# fan-host-board-v1_1-_WIP.net
KiCad netlist of a schematic drawn in EAGLE
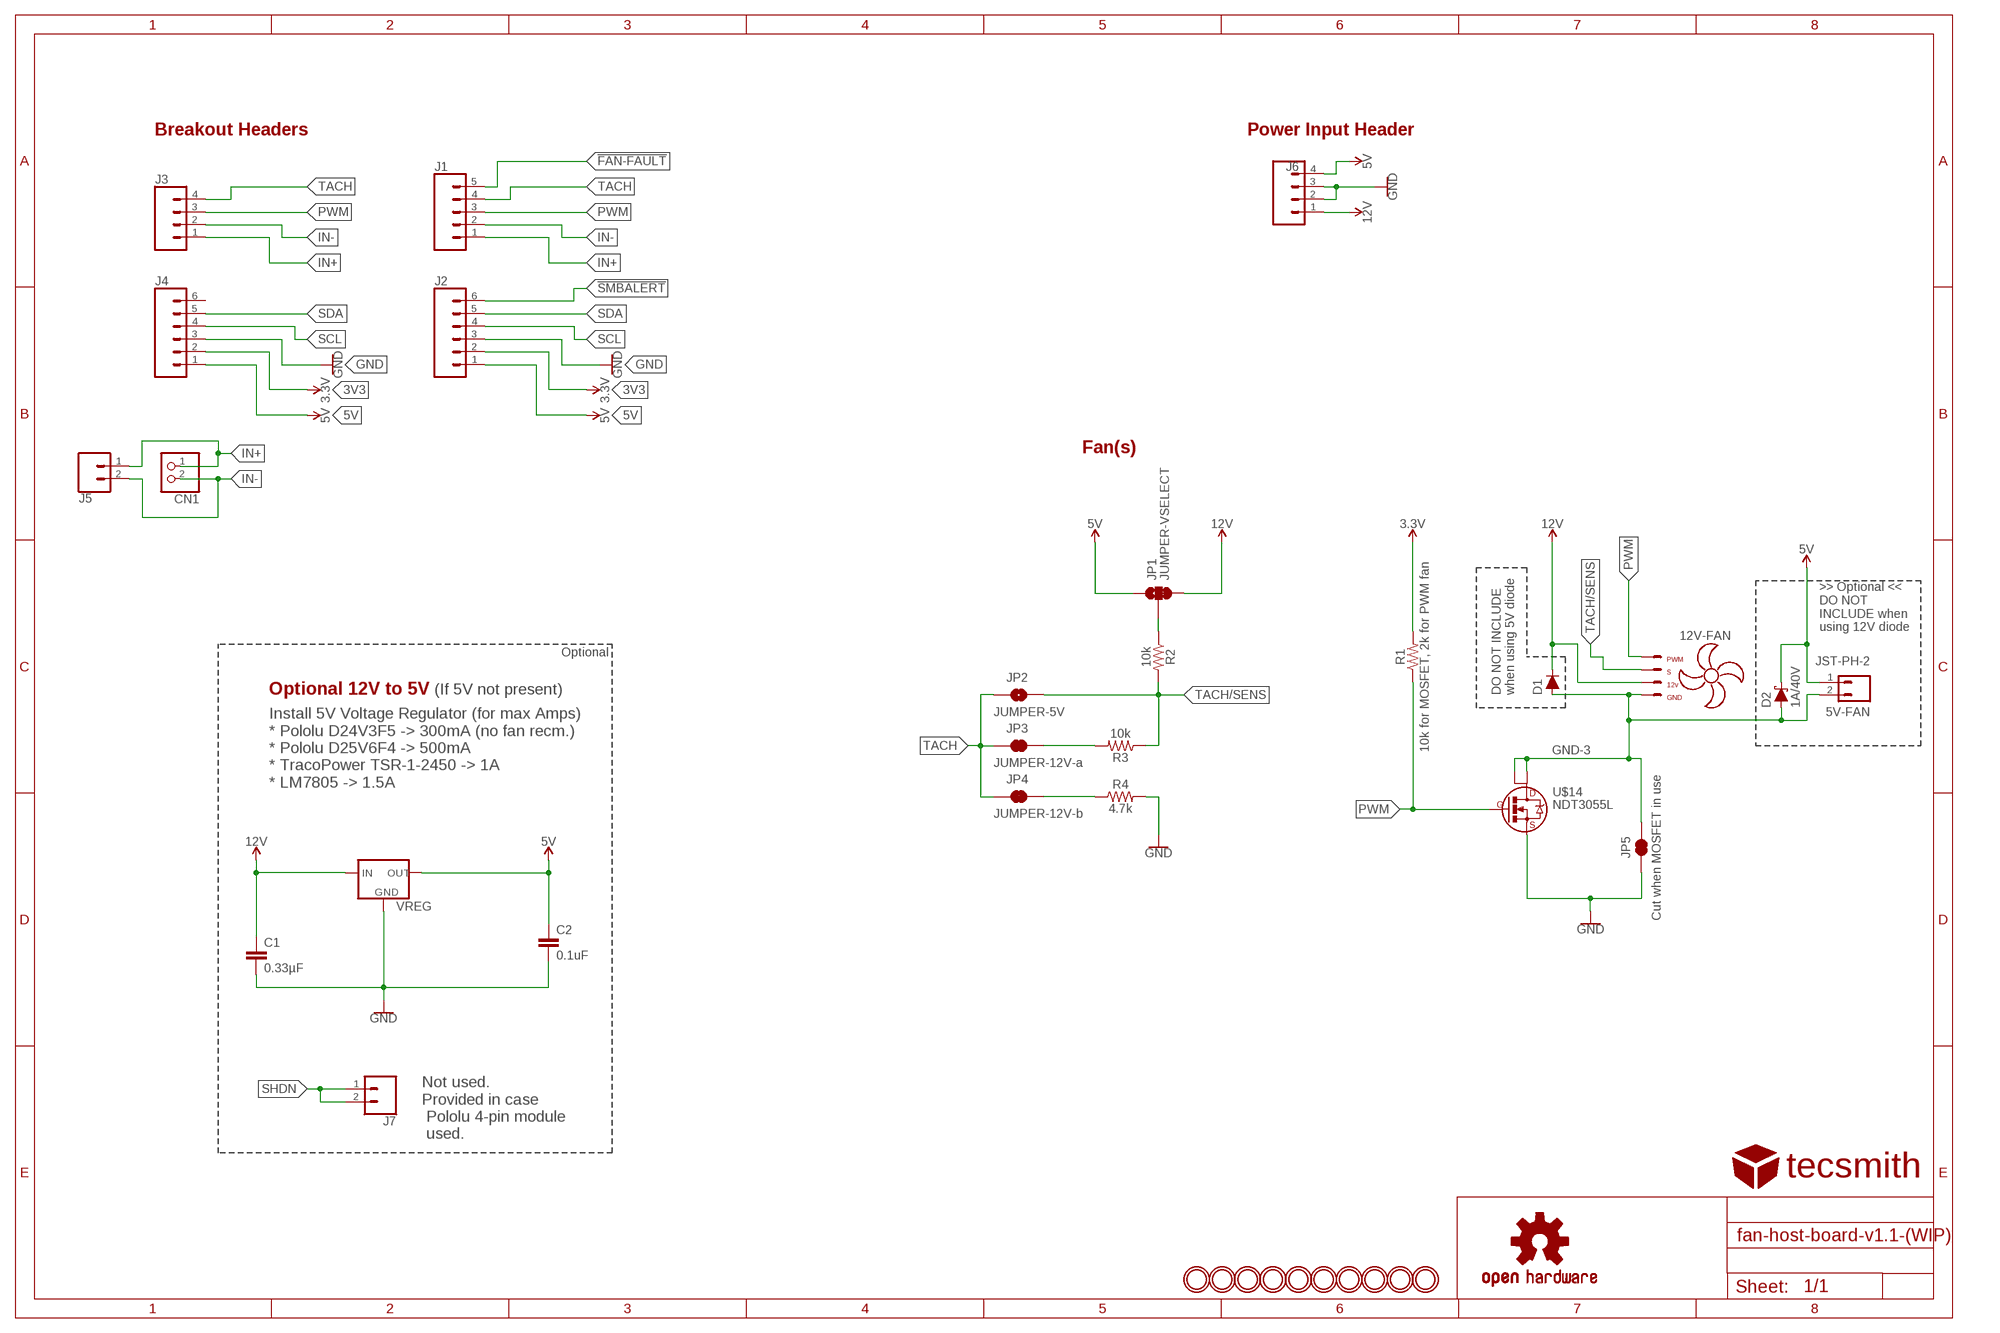
[diagram p0: schematic, sheet 1]

(export (version "E")
  (design (tool "Eeschema 10.0.6"))
  (components
    (comp (ref "5V-FAN")
      (value "JST-PH-2")
      (footprint "eagle-import:JST-PH2")
      (libsource (lib "eagle-import") (part "JST-PH-2"))
    )
    (comp (ref "12V-FAN")
      (value "KK-254-4KK-254")
      (footprint "eagle-import:MOLEX_47053-1000")
      (libsource (lib "eagle-import") (part "KK-254-4KK-254"))
    )
    (comp (ref "C1")
      (value "0.33µF")
      (footprint "eagle-import:0805")
      (libsource (lib "eagle-import") (part "0.33UF/330NF-0805-50V-10%"))
    )
    (comp (ref "C2")
      (value "0.1uF")
      (footprint "eagle-import:0603")
      (libsource (lib "eagle-import") (part "0.1UF-0603-25V-5%"))
    )
    (comp (ref "CN1")
      (value "JST_2PIN-THM")
      (footprint "eagle-import:JST-PH-2-THM")
      (libsource (lib "eagle-import") (part "JST_2PIN-THM"))
    )
    (comp (ref "D1")
      (value "200mA/100V")
      (footprint "eagle-import:DIODE-1N4148")
      (libsource (lib "eagle-import") (part "DIODE-1N4148"))
    )
    (comp (ref "D2")
      (value "1A/40V")
      (footprint "eagle-import:SMA-DIODE")
      (libsource (lib "eagle-import") (part "DIODE-SCHOTTKY-SS14"))
    )
    (comp (ref "J1")
      (value "CONN_05")
      (footprint "eagle-import:1X05")
      (libsource (lib "eagle-import") (part "CONN_05"))
    )
    (comp (ref "J2")
      (value "CONN_06SILK_FEMALE_PTH")
      (footprint "eagle-import:1X06")
      (libsource (lib "eagle-import") (part "CONN_06SILK_FEMALE_PTH"))
    )
    (comp (ref "J3")
      (value "CONN_04PTH")
      (footprint "eagle-import:1X04")
      (libsource (lib "eagle-import") (part "CONN_04PTH"))
    )
    (comp (ref "J4")
      (value "CONN_06SILK_FEMALE_PTH")
      (footprint "eagle-import:1X06")
      (libsource (lib "eagle-import") (part "CONN_06SILK_FEMALE_PTH"))
    )
    (comp (ref "J5")
      (value "CONN_02PTH3")
      (footprint "eagle-import:1X02_LONGPADS")
      (libsource (lib "eagle-import") (part "CONN_02PTH3"))
    )
    (comp (ref "J6")
      (value "CONN_04SCREW")
      (footprint "eagle-import:SCREWTERMINAL-3.5MM-4")
      (libsource (lib "eagle-import") (part "CONN_04SCREW"))
    )
    (comp (ref "J7")
      (value "CONN_021X02_NO_SILK")
      (footprint "eagle-import:1X02_NO_SILK")
      (libsource (lib "eagle-import") (part "CONN_021X02_NO_SILK"))
    )
    (comp (ref "JP1")
      (value "JUMPER-VSELECT")
      (footprint "eagle-import:SMT-JUMPER_3_1-NC_TRACE_SILK")
      (libsource (lib "eagle-import") (part "JUMPER-SMT_3_1-NC_TRACE_SILK"))
    )
    (comp (ref "JP2")
      (value "JUMPER-5V")
      (footprint "eagle-import:SMT-JUMPER_2_NO_SILK")
      (libsource (lib "eagle-import") (part "JUMPER-SMT_2_NO_NO_SILK"))
    )
    (comp (ref "JP3")
      (value "JUMPER-12V-a")
      (footprint "eagle-import:SMT-JUMPER_2_NC_TRACE_SILK")
      (libsource (lib "eagle-import") (part "JUMPER-SMT_2_NC_TRACE_SILK"))
    )
    (comp (ref "JP4")
      (value "JUMPER-12V-b")
      (footprint "eagle-import:SMT-JUMPER_2_NC_TRACE_SILK")
      (libsource (lib "eagle-import") (part "JUMPER-SMT_2_NC_TRACE_SILK"))
    )
    (comp (ref "JP5")
      (value "Cut when MOSFET in use")
      (footprint "eagle-import:SMT-JUMPER_2_NC_TRACE_NO-SILK")
      (libsource (lib "eagle-import") (part "JUMPER-SMT_2_NC_TRACE_NO-SILK"))
    )
    (comp (ref "LOGO1")
      (value "OSHW-LOGOS")
      (footprint "eagle-import:OSHW-LOGO-S")
      (libsource (lib "eagle-import") (part "OSHW-LOGOS"))
    )
    (comp (ref "R1")
      (value "10k for MOSFET, 2k for PWM fan")
      (footprint "eagle-import:0603")
      (libsource (lib "eagle-import") (part "2.2KOHM-0603-1/10W-1%"))
    )
    (comp (ref "R2")
      (value "10k")
      (footprint "eagle-import:0603")
      (libsource (lib "eagle-import") (part "10KOHM-0603-1/10W-1%"))
    )
    (comp (ref "R3")
      (value "10k")
      (footprint "eagle-import:0603")
      (libsource (lib "eagle-import") (part "10KOHM-0603-1/10W-1%"))
    )
    (comp (ref "R4")
      (value "4.7k")
      (footprint "eagle-import:0603")
      (libsource (lib "eagle-import") (part "4.7KOHM-0603-1/10W-1%"))
    )
    (comp (ref "U$1")
      (value "TECSMITH-LOGO")
      (footprint "eagle-import:TECSMITH-LOGO")
      (libsource (lib "eagle-import") (part "TECSMITH-LOGO"))
    )
    (comp (ref "U$2")
      (value "MOUNTINGHOLE2.5")
      (footprint "eagle-import:MOUNTINGHOLE_2.5_PLATED")
      (libsource (lib "eagle-import") (part "MOUNTINGHOLE2.5"))
    )
    (comp (ref "U$3")
      (value "MOUNTINGHOLE2.5")
      (footprint "eagle-import:MOUNTINGHOLE_2.5_PLATED")
      (libsource (lib "eagle-import") (part "MOUNTINGHOLE2.5"))
    )
    (comp (ref "U$4")
      (value "MOUNTINGHOLE2.5")
      (footprint "eagle-import:MOUNTINGHOLE_2.5_PLATED")
      (libsource (lib "eagle-import") (part "MOUNTINGHOLE2.5"))
    )
    (comp (ref "U$5")
      (value "MOUNTINGHOLE2.5")
      (footprint "eagle-import:MOUNTINGHOLE_2.5_PLATED")
      (libsource (lib "eagle-import") (part "MOUNTINGHOLE2.5"))
    )
    (comp (ref "U$6")
      (value "MOUNTINGHOLE2.5")
      (footprint "eagle-import:MOUNTINGHOLE_2.5_PLATED")
      (libsource (lib "eagle-import") (part "MOUNTINGHOLE2.5"))
    )
    (comp (ref "U$7")
      (value "MOUNTINGHOLE2.5")
      (footprint "eagle-import:MOUNTINGHOLE_2.5_PLATED")
      (libsource (lib "eagle-import") (part "MOUNTINGHOLE2.5"))
    )
    (comp (ref "U$8")
      (value "MOUNTINGHOLE2.5")
      (footprint "eagle-import:MOUNTINGHOLE_2.5_PLATED")
      (libsource (lib "eagle-import") (part "MOUNTINGHOLE2.5"))
    )
    (comp (ref "U$9")
      (value "MOUNTINGHOLE2.5")
      (footprint "eagle-import:MOUNTINGHOLE_2.5_PLATED")
      (libsource (lib "eagle-import") (part "MOUNTINGHOLE2.5"))
    )
    (comp (ref "U$10")
      (value "MOUNTINGHOLE2.5")
      (footprint "eagle-import:MOUNTINGHOLE_2.5_PLATED")
      (libsource (lib "eagle-import") (part "MOUNTINGHOLE2.5"))
    )
    (comp (ref "U$11")
      (value "MOUNTINGHOLE2.5")
      (footprint "eagle-import:MOUNTINGHOLE_2.5_PLATED")
      (libsource (lib "eagle-import") (part "MOUNTINGHOLE2.5"))
    )
    (comp (ref "U$14")
      (value "NDT3055L")
      (footprint "eagle-import:SOT223")
      (libsource (lib "eagle-import") (part "NDT3055L"))
    )
    (comp (ref "VREG")
      (value "TRACOPOWER-TSR-1")
      (footprint "eagle-import:TRACO-TSR-1")
      (libsource (lib "eagle-import") (part "TRACOPOWER-TSR-1"))
    )
  )
  (nets
    (net (code "1") (name "/GND-3") (class "Default")
      (node (ref "12V-FAN") (pin "1:GND") (pinfunction "1:GND_1:GND") (pintype "power_in"))
      (node (ref "5V-FAN") (pin "2") (pinfunction "2_2") (pintype "passive"))
      (node (ref "D1") (pin "A") (pinfunction "A_A") (pintype "passive"))
      (node (ref "D2") (pin "A") (pinfunction "A_A") (pintype "passive"))
      (node (ref "JP5") (pin "2") (pinfunction "2_2") (pintype "passive"))
      (node (ref "U$14") (pin "D") (pinfunction "D_D") (pintype "passive"))
      (node (ref "U$14") (pin "D2") (pinfunction "D2_D2") (pintype "passive"))
    )
    (net (code "2") (name "/~{FAN-FAULT}") (class "Default")
      (node (ref "J1") (pin "5") (pinfunction "5_5") (pintype "passive"))
    )
    (net (code "3") (name "/~{SMBALERT}") (class "Default")
      (node (ref "J2") (pin "6") (pinfunction "6_6") (pintype "passive"))
    )
    (net (code "4") (name "3V3") (class "Default")
      (node (ref "J2") (pin "2") (pinfunction "2_2") (pintype "passive"))
      (node (ref "J4") (pin "2") (pinfunction "2_2") (pintype "passive"))
      (node (ref "R1") (pin "2") (pinfunction "2_2") (pintype "passive"))
    )
    (net (code "5") (name "5V") (class "Default")
      (node (ref "5V-FAN") (pin "1") (pinfunction "1_1") (pintype "passive"))
      (node (ref "C2") (pin "1") (pinfunction "1_1") (pintype "passive"))
      (node (ref "D2") (pin "C") (pinfunction "C_C") (pintype "passive"))
      (node (ref "J2") (pin "1") (pinfunction "1_1") (pintype "passive"))
      (node (ref "J4") (pin "1") (pinfunction "1_1") (pintype "passive"))
      (node (ref "J6") (pin "4") (pinfunction "4_4") (pintype "passive"))
      (node (ref "JP1") (pin "1") (pinfunction "1_1") (pintype "passive"))
      (node (ref "VREG") (pin "P$+VOUT") (pinfunction "OUT_P$+VOUT") (pintype "output"))
    )
    (net (code "6") (name "12V") (class "Default")
      (node (ref "12V-FAN") (pin "2:+12VDC") (pinfunction "2:+12VDC_2:+12VDC") (pintype "power_in"))
      (node (ref "C1") (pin "1") (pinfunction "1_1") (pintype "passive"))
      (node (ref "D1") (pin "C") (pinfunction "C_C") (pintype "passive"))
      (node (ref "J6") (pin "1") (pinfunction "1_1") (pintype "passive"))
      (node (ref "JP1") (pin "3") (pinfunction "3_3") (pintype "passive"))
      (node (ref "VREG") (pin "P$+VIN") (pinfunction "IN_P$+VIN") (pintype "input"))
    )
    (net (code "7") (name "GND") (class "Default")
      (node (ref "C1") (pin "2") (pinfunction "2_2") (pintype "passive"))
      (node (ref "C2") (pin "2") (pinfunction "2_2") (pintype "passive"))
      (node (ref "J2") (pin "3") (pinfunction "3_3") (pintype "passive"))
      (node (ref "J4") (pin "3") (pinfunction "3_3") (pintype "passive"))
      (node (ref "J6") (pin "2") (pinfunction "2_2") (pintype "passive"))
      (node (ref "J6") (pin "3") (pinfunction "3_3") (pintype "passive"))
      (node (ref "JP5") (pin "1") (pinfunction "1_1") (pintype "passive"))
      (node (ref "R4") (pin "2") (pinfunction "2_2") (pintype "passive"))
      (node (ref "U$14") (pin "S") (pinfunction "S_S") (pintype "passive"))
      (node (ref "VREG") (pin "P$GND") (pinfunction "GND_P$GND") (pintype "power_in"))
    )
    (net (code "8") (name "IN+") (class "Default")
      (node (ref "CN1") (pin "1") (pinfunction "2_1") (pintype "passive"))
      (node (ref "J1") (pin "1") (pinfunction "1_1") (pintype "passive"))
      (node (ref "J3") (pin "1") (pinfunction "1_1") (pintype "passive"))
      (node (ref "J5") (pin "1") (pinfunction "1_1") (pintype "passive"))
    )
    (net (code "9") (name "IN-") (class "Default")
      (node (ref "CN1") (pin "2") (pinfunction "1_2") (pintype "passive"))
      (node (ref "J1") (pin "2") (pinfunction "2_2") (pintype "passive"))
      (node (ref "J3") (pin "2") (pinfunction "2_2") (pintype "passive"))
      (node (ref "J5") (pin "2") (pinfunction "2_2") (pintype "passive"))
    )
    (net (code "10") (name "Net-(JP1-Pad2)") (class "Default")
      (node (ref "JP1") (pin "2") (pinfunction "2_2") (pintype "passive"))
      (node (ref "R2") (pin "1") (pinfunction "1_1") (pintype "passive"))
    )
    (net (code "11") (name "Net-(JP3-Pad2)") (class "Default")
      (node (ref "JP3") (pin "2") (pinfunction "2_2") (pintype "passive"))
      (node (ref "R3") (pin "2") (pinfunction "2_2") (pintype "passive"))
    )
    (net (code "12") (name "Net-(JP4-Pad2)") (class "Default")
      (node (ref "JP4") (pin "2") (pinfunction "2_2") (pintype "passive"))
      (node (ref "R4") (pin "1") (pinfunction "1_1") (pintype "passive"))
    )
    (net (code "13") (name "PWM") (class "Default")
      (node (ref "12V-FAN") (pin "4:PWM") (pinfunction "4:PWM_4:PWM") (pintype "output"))
      (node (ref "J1") (pin "3") (pinfunction "3_3") (pintype "passive"))
      (node (ref "J3") (pin "3") (pinfunction "3_3") (pintype "passive"))
      (node (ref "R1") (pin "1") (pinfunction "1_1") (pintype "passive"))
      (node (ref "U$14") (pin "G") (pinfunction "G_G") (pintype "passive"))
    )
    (net (code "14") (name "SCL") (class "Default")
      (node (ref "J2") (pin "4") (pinfunction "4_4") (pintype "passive"))
      (node (ref "J4") (pin "4") (pinfunction "4_4") (pintype "passive"))
    )
    (net (code "15") (name "SDA") (class "Default")
      (node (ref "J2") (pin "5") (pinfunction "5_5") (pintype "passive"))
      (node (ref "J4") (pin "5") (pinfunction "5_5") (pintype "passive"))
    )
    (net (code "16") (name "SHDN") (class "Default")
      (node (ref "J7") (pin "1") (pinfunction "1_1") (pintype "passive"))
      (node (ref "J7") (pin "2") (pinfunction "2_2") (pintype "passive"))
    )
    (net (code "17") (name "TACH") (class "Default")
      (node (ref "J1") (pin "4") (pinfunction "4_4") (pintype "passive"))
      (node (ref "J3") (pin "4") (pinfunction "4_4") (pintype "passive"))
      (node (ref "JP2") (pin "1") (pinfunction "1_1") (pintype "passive"))
      (node (ref "JP3") (pin "1") (pinfunction "1_1") (pintype "passive"))
      (node (ref "JP4") (pin "1") (pinfunction "1_1") (pintype "passive"))
    )
    (net (code "18") (name "TACH{slash}SENS") (class "Default")
      (node (ref "12V-FAN") (pin "3:TACH") (pinfunction "3:TACH_3:TACH") (pintype "input"))
      (node (ref "JP2") (pin "2") (pinfunction "2_2") (pintype "passive"))
      (node (ref "R2") (pin "2") (pinfunction "2_2") (pintype "passive"))
      (node (ref "R3") (pin "1") (pinfunction "1_1") (pintype "passive"))
    )
    (net (code "19") (name "unconnected-(J4-Pad6)") (class "Default")
      (node (ref "J4") (pin "6") (pinfunction "6_6") (pintype "passive"))
    )
  )
)
